# can_unisolated.net
KiCad netlist of a schematic drawn in Altium Designer
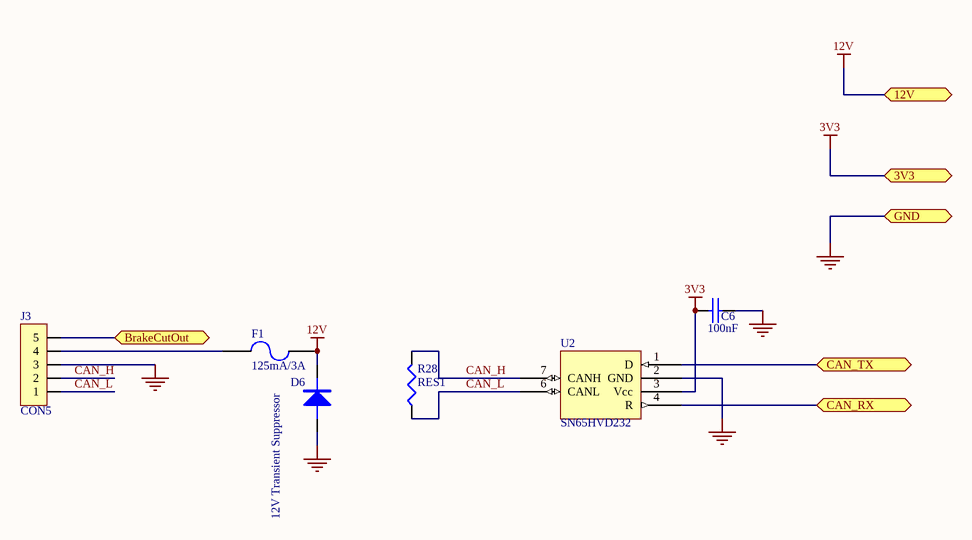
[diagram p0: can_unisolated.SchDoc]

(export (version "E")
  (design (tool "Eeschema 10.0.6"))
  (components
    (comp (ref "C6")
      (value "100nF")
      (footprint "0603")
      (description "Capacitor")
      (libsource (lib "*") (part "CAP"))
    )
    (comp (ref "D6")
      (value "12V Transient Suppressor")
      (footprint "SMA")
      (description "Diode")
      (libsource (lib "RCLDQ") (part "DIODE"))
    )
    (comp (ref "F1")
      (value "125mA/3A")
      (footprint "LITTELFUSE-154")
      (description "Fuse")
      (libsource (lib "*") (part "FUSE2"))
    )
    (comp (ref "J3")
      (value "CON5")
      (footprint "ENG.1B.305.CLL")
      (description "Connector")
      (libsource (lib "Connectors") (part "CON5"))
    )
    (comp (ref "R28")
      (value "RES1")
      (footprint "0603")
      (description "Resistor")
      (libsource (lib "RCLDQ") (part "RES1"))
    )
    (comp (ref "U2")
      (value "SN65HVD232")
      (footprint "SO8")
      (description "3.3V CAN Transciever")
      (libsource (lib "*") (part "SN65HVD232"))
    )
  )
  (nets
    (net (code "1") (name "/BrakeCutOut") (class "Default")
      (node (ref "J3") (pin "5") (pinfunction "5_5") (pintype "passive"))
    )
    (net (code "2") (name "/CAN_H") (class "Default")
      (node (ref "J3") (pin "2") (pinfunction "2_2") (pintype "passive"))
      (node (ref "R28") (pin "2") (pinfunction "2_2") (pintype "passive"))
      (node (ref "U2") (pin "7") (pinfunction "CANH_7") (pintype "bidirectional"))
    )
    (net (code "3") (name "/CAN_L") (class "Default")
      (node (ref "J3") (pin "1") (pinfunction "1_1") (pintype "passive"))
      (node (ref "R28") (pin "1") (pinfunction "1_1") (pintype "passive"))
      (node (ref "U2") (pin "6") (pinfunction "CANL_6") (pintype "bidirectional"))
    )
    (net (code "4") (name "/CAN_RX") (class "Default")
      (node (ref "U2") (pin "4") (pinfunction "R_4") (pintype "output"))
    )
    (net (code "5") (name "/CAN_TX") (class "Default")
      (node (ref "U2") (pin "1") (pinfunction "D_1") (pintype "input"))
    )
    (net (code "6") (name "3V3") (class "Default")
      (node (ref "C6") (pin "2") (pinfunction "2_2") (pintype "passive"))
      (node (ref "U2") (pin "3") (pinfunction "Vcc_3") (pintype "power_in"))
    )
    (net (code "7") (name "12V") (class "Default")
      (node (ref "D6") (pin "K") (pinfunction "K_K") (pintype "passive"))
      (node (ref "F1") (pin "2") (pinfunction "2_2") (pintype "passive"))
    )
    (net (code "8") (name "GND") (class "Default")
      (node (ref "C6") (pin "1") (pinfunction "1_1") (pintype "passive"))
      (node (ref "D6") (pin "A") (pinfunction "A_A") (pintype "passive"))
      (node (ref "J3") (pin "3") (pinfunction "3_3") (pintype "passive"))
      (node (ref "U2") (pin "2") (pinfunction "GND_2") (pintype "power_in"))
    )
    (net (code "9") (name "Net-(F1-Pad1)") (class "Default")
      (node (ref "F1") (pin "1") (pinfunction "1_1") (pintype "passive"))
      (node (ref "J3") (pin "4") (pinfunction "4_4") (pintype "passive"))
    )
  )
)
